# Sheet2.net
KiCad netlist of a schematic drawn in Altium Designer
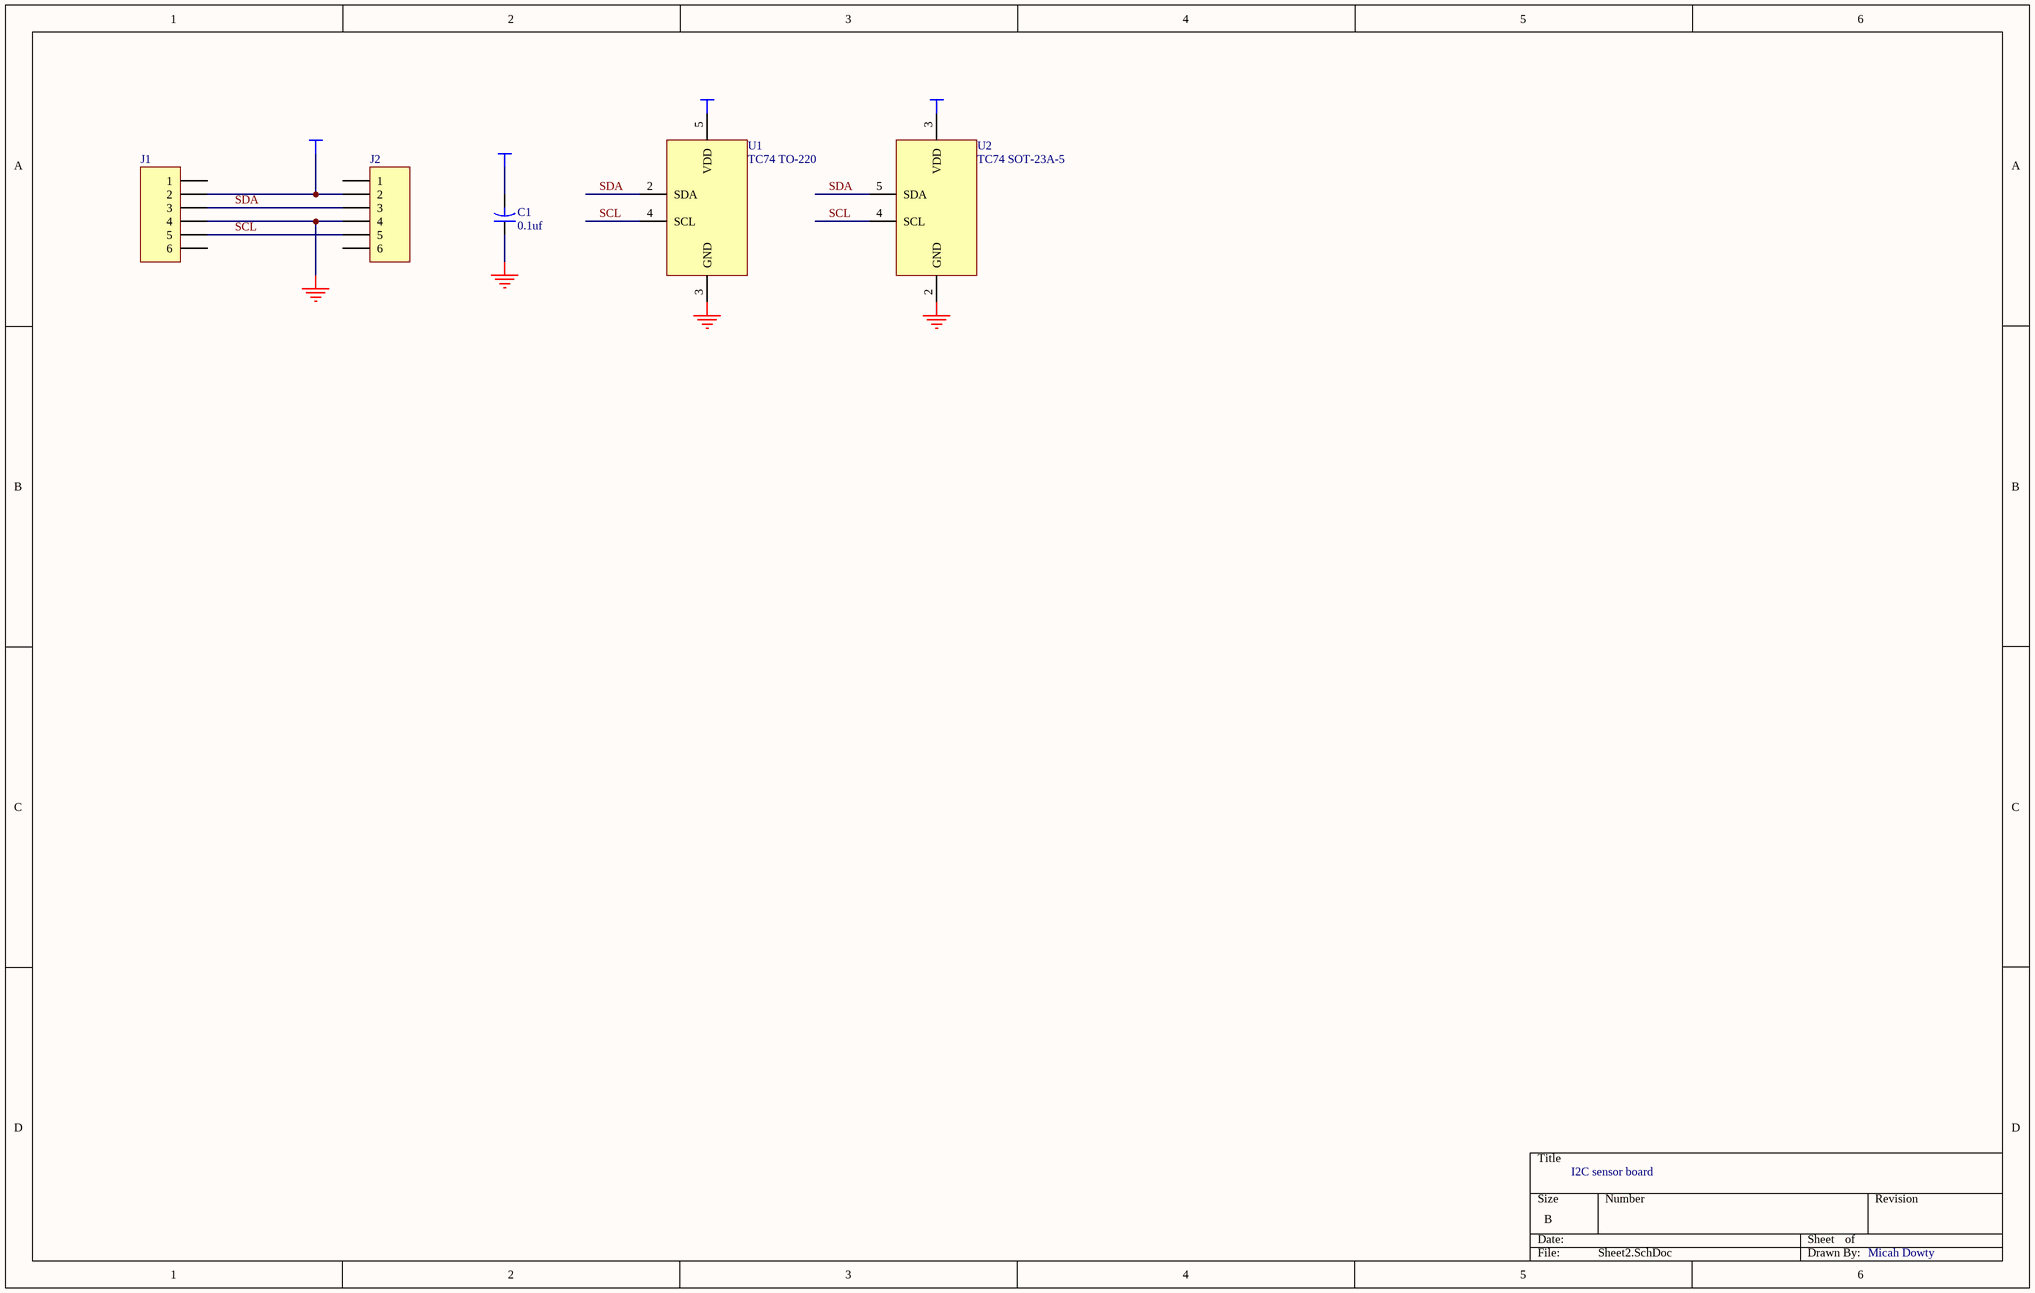
[diagram p0: Sheet2.SchDoc]

(export (version "E")
  (design (tool "Eeschema 10.0.6"))
  (components
    (comp (ref "C1")
      (value "0.1uf")
      (footprint "CAPR5-4X5")
      (description "Capacitor")
      (fields (field (name "MANUFACTURER") "Generic Components") (field (name "PUBLISHER") "Altium Limited"))
      (libsource (lib "Miscellaneous Devices") (part "Cap2"))
    )
    (comp (ref "J1")
      (value "~")
      (footprint "RJ11")
      (description "Header, 6-Pin")
      (fields (field (name "MANUFACTURER") "Generic Components") (field (name "PUBLISHER") "Altium Limited"))
      (libsource (lib "Miscellaneous Connectors") (part "Header 6"))
    )
    (comp (ref "J2")
      (value "~")
      (footprint "RJ11")
      (description "Header, 6-Pin")
      (fields (field (name "MANUFACTURER") "Generic Components") (field (name "PUBLISHER") "Altium Limited"))
      (libsource (lib "") (part "Header 6_1"))
    )
    (comp (ref "U1")
      (value "TC74 TO-220")
      (footprint "SFM-T5/A4.6V-NOTEXT")
      (libsource (lib "parts") (part "TC74 TO-220"))
    )
    (comp (ref "U2")
      (value "TC74 SOT-23A-5")
      (footprint "SO-G5/Z3.6")
      (libsource (lib "parts") (part "TC74 SOT-23A-5"))
    )
  )
  (nets
    (net (code "1") (name "/SCL") (class "Default")
      (node (ref "J1") (pin "5") (pinfunction "5_5") (pintype "passive"))
      (node (ref "J2") (pin "5") (pinfunction "5_5") (pintype "passive"))
      (node (ref "U1") (pin "4") (pinfunction "SCL_4") (pintype "passive"))
      (node (ref "U2") (pin "4") (pinfunction "SCL_4") (pintype "passive"))
    )
    (net (code "2") (name "/SDA") (class "Default")
      (node (ref "J1") (pin "3") (pinfunction "3_3") (pintype "passive"))
      (node (ref "J2") (pin "3") (pinfunction "3_3") (pintype "passive"))
      (node (ref "U1") (pin "2") (pinfunction "SDA_2") (pintype "passive"))
      (node (ref "U2") (pin "5") (pinfunction "SDA_5") (pintype "passive"))
    )
    (net (code "3") (name "GND") (class "Default")
      (node (ref "C1") (pin "1") (pinfunction "1_1") (pintype "passive"))
      (node (ref "J1") (pin "4") (pinfunction "4_4") (pintype "passive"))
      (node (ref "J2") (pin "4") (pinfunction "4_4") (pintype "passive"))
      (node (ref "U1") (pin "3") (pinfunction "GND_3") (pintype "passive"))
      (node (ref "U2") (pin "2") (pinfunction "GND_2") (pintype "passive"))
    )
    (net (code "4") (name "VCC") (class "Default")
      (node (ref "C1") (pin "2") (pinfunction "2_2") (pintype "passive"))
      (node (ref "J1") (pin "2") (pinfunction "2_2") (pintype "passive"))
      (node (ref "J2") (pin "2") (pinfunction "2_2") (pintype "passive"))
      (node (ref "U1") (pin "5") (pinfunction "VDD_5") (pintype "passive"))
      (node (ref "U2") (pin "3") (pinfunction "VDD_3") (pintype "passive"))
    )
    (net (code "5") (name "unconnected-(J1-Pad1)") (class "Default")
      (node (ref "J1") (pin "1") (pinfunction "1_1") (pintype "passive"))
    )
    (net (code "6") (name "unconnected-(J1-Pad6)") (class "Default")
      (node (ref "J1") (pin "6") (pinfunction "6_6") (pintype "passive"))
    )
    (net (code "7") (name "unconnected-(J2-Pad1)") (class "Default")
      (node (ref "J2") (pin "1") (pinfunction "1_1") (pintype "passive"))
    )
    (net (code "8") (name "unconnected-(J2-Pad6)") (class "Default")
      (node (ref "J2") (pin "6") (pinfunction "6_6") (pintype "passive"))
    )
  )
)
